# cassowari-original.net
KiCad netlist of a schematic drawn in EAGLE
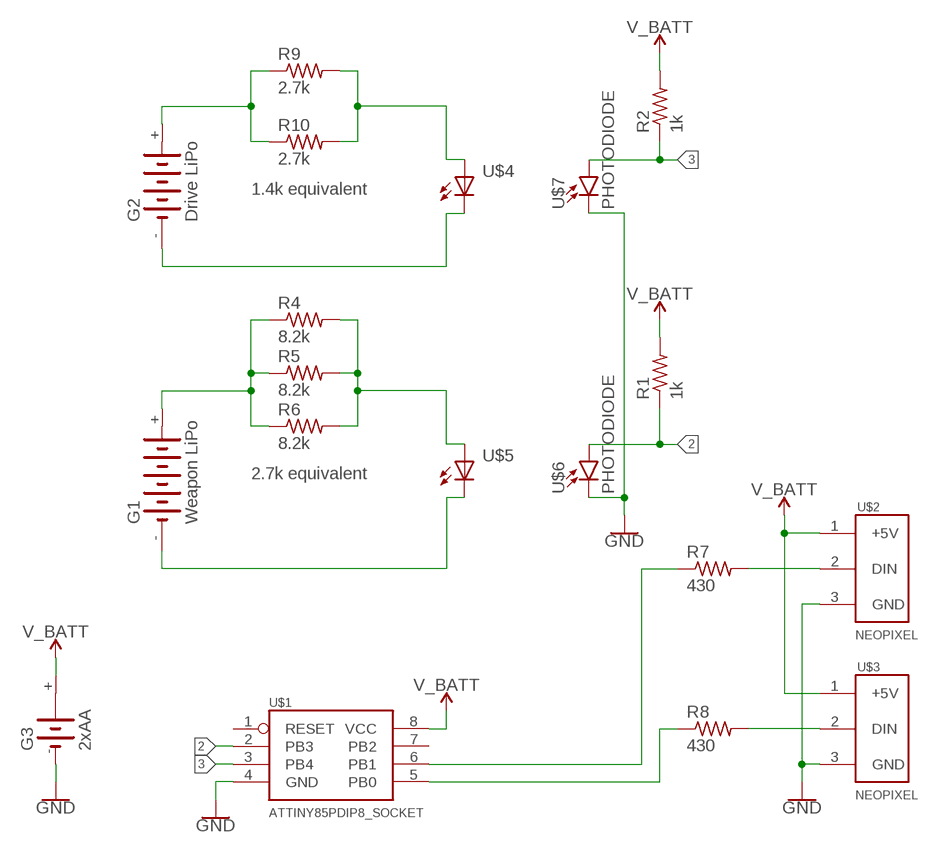
[diagram p0: schematic, sheet 1]

(export (version "E")
  (design (tool "Eeschema 10.0.6"))
  (components
    (comp (ref "G1")
      (value "Weapon LiPo")
      (footprint "eagle-import:NC2M")
      (libsource (lib "eagle-import") (part "NC2M"))
    )
    (comp (ref "G2")
      (value "Drive LiPo")
      (footprint "eagle-import:NC1M")
      (libsource (lib "eagle-import") (part "NC1M4V8"))
    )
    (comp (ref "G3")
      (value "2xAA")
      (footprint "eagle-import:NC2M")
      (libsource (lib "eagle-import") (part "NC2M2V4"))
    )
    (comp (ref "R1")
      (value "1k")
      (footprint "eagle-import:VMTA55")
      (libsource (lib "eagle-import") (part "R-US_VMTA55"))
    )
    (comp (ref "R2")
      (value "1k")
      (footprint "eagle-import:VMTA55")
      (libsource (lib "eagle-import") (part "R-US_VMTA55"))
    )
    (comp (ref "R4")
      (value "8.2k")
      (footprint "eagle-import:VMTA55")
      (libsource (lib "eagle-import") (part "R-US_VMTA55"))
    )
    (comp (ref "R5")
      (value "8.2k")
      (footprint "eagle-import:VMTA55")
      (libsource (lib "eagle-import") (part "R-US_VMTA55"))
    )
    (comp (ref "R6")
      (value "8.2k")
      (footprint "eagle-import:VMTA55")
      (libsource (lib "eagle-import") (part "R-US_VMTA55"))
    )
    (comp (ref "R7")
      (value "430")
      (footprint "eagle-import:VMTA55")
      (libsource (lib "eagle-import") (part "R-US_VMTA55"))
    )
    (comp (ref "R8")
      (value "430")
      (footprint "eagle-import:VMTA55")
      (libsource (lib "eagle-import") (part "R-US_VMTA55"))
    )
    (comp (ref "R9")
      (value "2.7k")
      (footprint "eagle-import:VMTA55")
      (libsource (lib "eagle-import") (part "R-US_VMTA55"))
    )
    (comp (ref "R10")
      (value "2.7k")
      (footprint "eagle-import:VMTA55")
      (libsource (lib "eagle-import") (part "R-US_VMTA55"))
    )
    (comp (ref "U$1")
      (value "ATTINY85PDIP8_SOCKET")
      (footprint "eagle-import:SOCKET-08")
      (libsource (lib "eagle-import") (part "ATTINY85PDIP8_SOCKET"))
    )
    (comp (ref "U$2")
      (value "NEOPIXEL")
      (footprint "eagle-import:NEOPIXEL_PINHEAD")
      (libsource (lib "eagle-import") (part "NEOPIXEL"))
    )
    (comp (ref "U$3")
      (value "NEOPIXEL")
      (footprint "eagle-import:NEOPIXEL_PINHEAD")
      (libsource (lib "eagle-import") (part "NEOPIXEL"))
    )
    (comp (ref "U$4")
      (value "LED")
      (footprint "eagle-import:LED_3MM_HORIZ")
      (libsource (lib "eagle-import") (part "LED"))
    )
    (comp (ref "U$5")
      (value "LED")
      (footprint "eagle-import:LED_3MM_HORIZ")
      (libsource (lib "eagle-import") (part "LED"))
    )
    (comp (ref "U$6")
      (value "PHOTODIODE")
      (footprint "eagle-import:LED_3MM_HORIZ")
      (libsource (lib "eagle-import") (part "PHOTODIODE"))
    )
    (comp (ref "U$7")
      (value "PHOTODIODE")
      (footprint "eagle-import:LED_3MM_HORIZ")
      (libsource (lib "eagle-import") (part "PHOTODIODE"))
    )
  )
  (nets
    (net (code "1") (name "2") (class "Default")
      (node (ref "R1") (pin "1") (pinfunction "1_1") (pintype "passive"))
      (node (ref "U$1") (pin "2") (pinfunction "PB3_2") (pintype "bidirectional"))
      (node (ref "U$6") (pin "A") (pinfunction "A_A") (pintype "passive"))
    )
    (net (code "2") (name "3") (class "Default")
      (node (ref "R2") (pin "1") (pinfunction "1_1") (pintype "passive"))
      (node (ref "U$1") (pin "3") (pinfunction "PB4_3") (pintype "bidirectional"))
      (node (ref "U$7") (pin "A") (pinfunction "A_A") (pintype "passive"))
    )
    (net (code "3") (name "GND") (class "Default")
      (node (ref "G3") (pin "-") (pinfunction "-_-") (pintype "passive"))
      (node (ref "U$1") (pin "4") (pinfunction "GND_4") (pintype "power_in"))
      (node (ref "U$2") (pin "3") (pinfunction "GND_3") (pintype "power_in"))
      (node (ref "U$3") (pin "3") (pinfunction "GND_3") (pintype "power_in"))
      (node (ref "U$6") (pin "K") (pinfunction "C_K") (pintype "passive"))
      (node (ref "U$7") (pin "K") (pinfunction "C_K") (pintype "passive"))
    )
    (net (code "4") (name "Net-(G1-Pad+)") (class "Default")
      (node (ref "G1") (pin "+") (pinfunction "+_+") (pintype "passive"))
      (node (ref "R4") (pin "1") (pinfunction "1_1") (pintype "passive"))
      (node (ref "R5") (pin "1") (pinfunction "1_1") (pintype "passive"))
      (node (ref "R6") (pin "1") (pinfunction "1_1") (pintype "passive"))
    )
    (net (code "5") (name "Net-(G1-Pad-)") (class "Default")
      (node (ref "G1") (pin "-") (pinfunction "-_-") (pintype "passive"))
      (node (ref "U$5") (pin "K") (pinfunction "K_K") (pintype "passive"))
    )
    (net (code "6") (name "Net-(G2-Pad+)") (class "Default")
      (node (ref "G2") (pin "+") (pinfunction "+_+") (pintype "passive"))
      (node (ref "R10") (pin "1") (pinfunction "1_1") (pintype "passive"))
      (node (ref "R9") (pin "1") (pinfunction "1_1") (pintype "passive"))
    )
    (net (code "7") (name "Net-(G2-Pad-)") (class "Default")
      (node (ref "G2") (pin "-") (pinfunction "-_-") (pintype "passive"))
      (node (ref "U$4") (pin "K") (pinfunction "K_K") (pintype "passive"))
    )
    (net (code "8") (name "Net-(R4-Pad2)") (class "Default")
      (node (ref "R4") (pin "2") (pinfunction "2_2") (pintype "passive"))
      (node (ref "R5") (pin "2") (pinfunction "2_2") (pintype "passive"))
      (node (ref "R6") (pin "2") (pinfunction "2_2") (pintype "passive"))
      (node (ref "U$5") (pin "A") (pinfunction "A_A") (pintype "passive"))
    )
    (net (code "9") (name "Net-(R10-Pad2)") (class "Default")
      (node (ref "R10") (pin "2") (pinfunction "2_2") (pintype "passive"))
      (node (ref "R9") (pin "2") (pinfunction "2_2") (pintype "passive"))
      (node (ref "U$4") (pin "A") (pinfunction "A_A") (pintype "passive"))
    )
    (net (code "10") (name "Net-(U$1-PB0)") (class "Default")
      (node (ref "R8") (pin "1") (pinfunction "1_1") (pintype "passive"))
      (node (ref "U$1") (pin "5") (pinfunction "PB0_5") (pintype "bidirectional"))
    )
    (net (code "11") (name "Net-(U$1-PB1)") (class "Default")
      (node (ref "R7") (pin "1") (pinfunction "1_1") (pintype "passive"))
      (node (ref "U$1") (pin "6") (pinfunction "PB1_6") (pintype "bidirectional"))
    )
    (net (code "12") (name "Net-(U$2-DIN)") (class "Default")
      (node (ref "R7") (pin "2") (pinfunction "2_2") (pintype "passive"))
      (node (ref "U$2") (pin "2") (pinfunction "DIN_2") (pintype "input"))
    )
    (net (code "13") (name "Net-(U$3-DIN)") (class "Default")
      (node (ref "R8") (pin "2") (pinfunction "2_2") (pintype "passive"))
      (node (ref "U$3") (pin "2") (pinfunction "DIN_2") (pintype "input"))
    )
    (net (code "14") (name "V_BATT") (class "Default")
      (node (ref "G3") (pin "+") (pinfunction "+_+") (pintype "passive"))
      (node (ref "R1") (pin "2") (pinfunction "2_2") (pintype "passive"))
      (node (ref "R2") (pin "2") (pinfunction "2_2") (pintype "passive"))
      (node (ref "U$1") (pin "8") (pinfunction "VCC_8") (pintype "power_in"))
      (node (ref "U$2") (pin "1") (pinfunction "+5V_1") (pintype "power_in"))
      (node (ref "U$3") (pin "1") (pinfunction "+5V_1") (pintype "power_in"))
    )
    (net (code "15") (name "unconnected-(G1-+-Pad+@1)") (class "Default")
      (node (ref "G1") (pin "+@1") (pinfunction "+_+@1") (pintype "passive"))
    )
    (net (code "16") (name "unconnected-(G2-+-Pad+@1)") (class "Default")
      (node (ref "G2") (pin "+@1") (pinfunction "+_+@1") (pintype "passive"))
    )
    (net (code "17") (name "unconnected-(G3-+-Pad+@1)") (class "Default")
      (node (ref "G3") (pin "+@1") (pinfunction "+_+@1") (pintype "passive"))
    )
    (net (code "18") (name "unconnected-(U$1-PB2-Pad7)") (class "Default")
      (node (ref "U$1") (pin "7") (pinfunction "PB2_7") (pintype "bidirectional"))
    )
    (net (code "19") (name "unconnected-(U$1-RESET-Pad1)") (class "Default")
      (node (ref "U$1") (pin "1") (pinfunction "RESET_1") (pintype "input"))
    )
  )
)
